# BANK14.net
KiCad netlist of a schematic drawn in Altium Designer
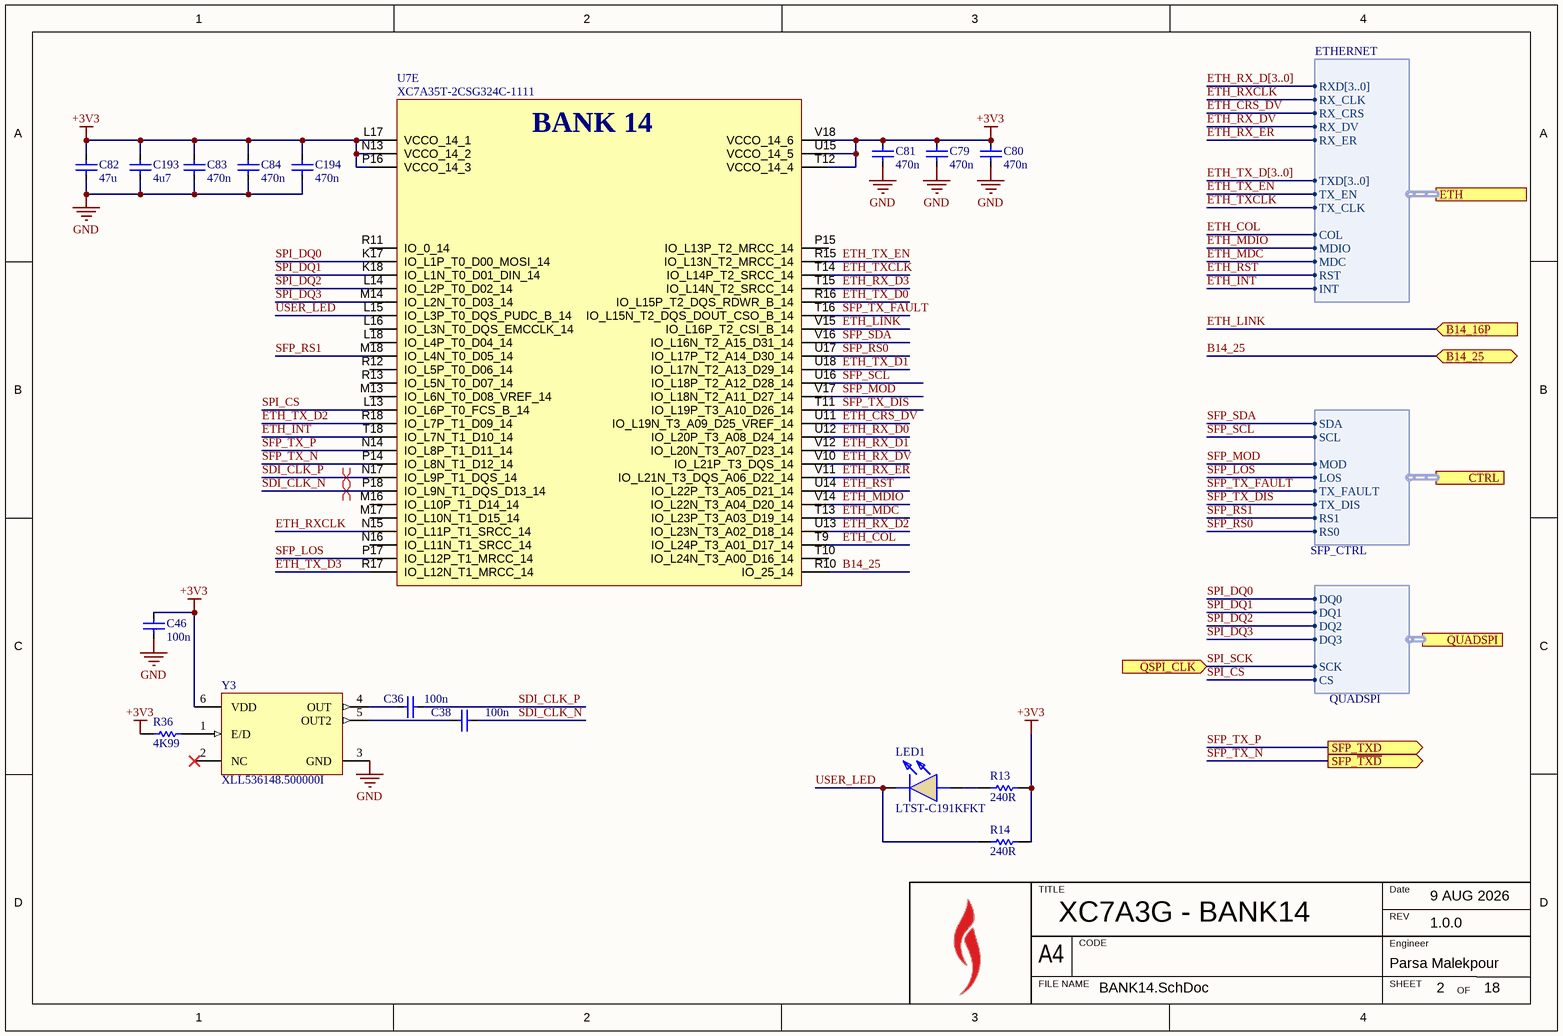
[diagram p0: BANK14.SchDoc]

(export (version "E")
  (design (tool "Eeschema 10.0.6"))
  (components
    (comp (ref "C36")
      (value "100n")
      (footprint "FP-C1005-050-0_05-IPC_C")
      (description "MLCC 100nF ±10% 50V X7R SMD 0402")
      (fields (field (name "VOLTAGE") "50V") (field (name "TOLERANCE") "10%"))
      (libsource (lib "Schlib1") (part "C1005X7R1H104K050BB"))
    )
    (comp (ref "C38")
      (value "100n")
      (footprint "FP-C1005-050-0_05-IPC_C")
      (description "MLCC 100nF ±10% 50V X7R SMD 0402")
      (fields (field (name "VOLTAGE") "50V") (field (name "TOLERANCE") "10%"))
      (libsource (lib "Schlib1") (part "C1005X7R1H104K050BB"))
    )
    (comp (ref "C46")
      (value "100n")
      (footprint "FP-C1005-050-0_05-IPC_C")
      (description "MLCC 100nF ±10% 50V X7R SMD 0402")
      (fields (field (name "VOLTAGE") "50V") (field (name "TOLERANCE") "10%"))
      (libsource (lib "Schlib1") (part "C1005X7R1H104K050BB"))
    )
    (comp (ref "C79")
      (value "470n")
      (footprint "pcblib1:FP-C1005-050-0_05-IPC_C")
      (description "Multilayer Ceramic Capacitors 470nF ±10% 25V X5R SMD 0402")
      (fields (field (name "VOLTAGE") "25V") (field (name "TOLERANCE") "10%"))
      (libsource (lib "Schlib1") (part "C1005X5R1E474K050BB"))
    )
    (comp (ref "C80")
      (value "470n")
      (footprint "pcblib1:FP-C1005-050-0_05-IPC_C")
      (description "Multilayer Ceramic Capacitors 470nF ±10% 25V X5R SMD 0402")
      (fields (field (name "VOLTAGE") "25V") (field (name "TOLERANCE") "10%"))
      (libsource (lib "Schlib1") (part "C1005X5R1E474K050BB"))
    )
    (comp (ref "C81")
      (value "470n")
      (footprint "pcblib1:FP-C1005-050-0_05-IPC_C")
      (description "Multilayer Ceramic Capacitors 470nF ±10% 25V X5R SMD 0402")
      (fields (field (name "VOLTAGE") "25V") (field (name "TOLERANCE") "10%"))
      (libsource (lib "Schlib1") (part "C1005X5R1E474K050BB"))
    )
    (comp (ref "C82")
      (value "47u")
      (footprint "pcblib1:FP-C2012-125-0_2-IPC_C")
      (description "47μF ±20% 10V X5R SMD 0805 Multilayer Ceramic Capacitors")
      (fields (field (name "VOLTAGE") "10V") (field (name "TOLERANCE") "20%"))
      (libsource (lib "Schlib1") (part "C2012X5R1A476M125AC"))
    )
    (comp (ref "C83")
      (value "470n")
      (footprint "pcblib1:FP-C1005-050-0_05-IPC_C")
      (description "Multilayer Ceramic Capacitors 470nF ±10% 25V X5R SMD 0402")
      (fields (field (name "VOLTAGE") "25V") (field (name "TOLERANCE") "10%"))
      (libsource (lib "Schlib1") (part "C1005X5R1E474K050BB"))
    )
    (comp (ref "C84")
      (value "470n")
      (footprint "pcblib1:FP-C1005-050-0_05-IPC_C")
      (description "Multilayer Ceramic Capacitors 470nF ±10% 25V X5R SMD 0402")
      (fields (field (name "VOLTAGE") "25V") (field (name "TOLERANCE") "10%"))
      (libsource (lib "Schlib1") (part "C1005X5R1E474K050BB"))
    )
    (comp (ref "C193")
      (value "4u7")
      (footprint "FP-C1005-050-0_20-0_10-IPC_C")
      (description "4.7UF 10V X5R 0402")
      (fields (field (name "TOLERANCE") "10%") (field (name "PART NUMBER") "C1005X5R1A475K050BE"))
      (libsource (lib "Schlib1") (part "C1005X5R1A475K050BE"))
    )
    (comp (ref "C194")
      (value "470n")
      (footprint "pcblib1:FP-C1005-050-0_05-IPC_C")
      (description "Multilayer Ceramic Capacitors 470nF ±10% 25V X5R SMD 0402")
      (fields (field (name "VOLTAGE") "25V") (field (name "TOLERANCE") "10%"))
      (libsource (lib "Schlib1") (part "C1005X5R1E474K050BB"))
    )
    (comp (ref "LED1")
      (value "LTST-C191KFKT")
      (footprint "LEDC1608X55N")
      (description "LED")
      (fields (field (name "MOUSER PART NUMBER") "859-LTST-C191KFKT") (field (name "MANUFACTURER") "Lite-On"))
      (libsource (lib "Schlib1") (part "LTST-C191KFKT"))
    )
    (comp (ref "R13")
      (value "240R")
      (footprint "pcblib1:RESC1005X40X25LL05T10")
      (description "240R 0.063W 1% 0402 (1005 Metric)  SMD")
      (fields (field (name "POWER") "0.063 W") (field (name "TOLERANCE") "1 %"))
      (libsource (lib "Schlib1") (part "RC0402FR-07240RL"))
    )
    (comp (ref "R14")
      (value "240R")
      (footprint "pcblib1:RESC1005X40X25LL05T10")
      (description "240R 0.063W 1% 0402 (1005 Metric)  SMD")
      (fields (field (name "POWER") "0.063 W") (field (name "TOLERANCE") "1 %"))
      (libsource (lib "Schlib1") (part "RC0402FR-07240RL"))
    )
    (comp (ref "R36")
      (value "4K99")
      (footprint "RESC1005X40X25LL05T10")
      (fields (field (name "MANUFACTURER") "Yageo / Phycomp") (field (name "PART NUMBER") "RC0402FR-074K99L"))
      (libsource (lib "Schlib1") (part "RC0402FR-074K99L"))
    )
    (comp (ref "U7")
      (value "XC7A35T-2CSG324C-1111")
      (footprint "PCBLIB1:BGA324C80P18X18_1500X1500X150")
      (description "Integrated Circuit")
      (fields
        (field (name "MANUFACTURER_PART_NUMBER") "XC7A35T-2CSG324C")
        (field (name "MOUSER PART NUMBER") "217-XC7A35T-2CSG324C")
      )
      (libsource (lib "Schlib1") (part "XC7A35T-2CSG324C-1111"))
    )
    (comp (ref "Y3")
      (value "XLL536148.500000I")
      (footprint "JS6_MFG")
      (description "Oscillator, 148.5Mhz, Lvds, 5Mm X 3.2Mm Rohs Compliant: Yes")
      (libsource (lib "Schlib1") (part "XLL536148.500000I"))
    )
  )
  (nets
    (net (code "4") (name "+3V3") (class "Default")
      (node (ref "C193") (pin "1") (pinfunction "1_1") (pintype "passive"))
      (node (ref "C194") (pin "1") (pinfunction "1_1") (pintype "passive"))
      (node (ref "C46") (pin "2") (pinfunction "2_2") (pintype "passive"))
      (node (ref "C79") (pin "1") (pinfunction "1_1") (pintype "passive"))
      (node (ref "C80") (pin "1") (pinfunction "1_1") (pintype "passive"))
      (node (ref "C81") (pin "1") (pinfunction "1_1") (pintype "passive"))
      (node (ref "C82") (pin "1") (pinfunction "1_1") (pintype "passive"))
      (node (ref "C83") (pin "1") (pinfunction "1_1") (pintype "passive"))
      (node (ref "C84") (pin "1") (pinfunction "1_1") (pintype "passive"))
      (node (ref "R13") (pin "2") (pinfunction "2_2") (pintype "passive"))
      (node (ref "R14") (pin "2") (pinfunction "2_2") (pintype "passive"))
      (node (ref "R36") (pin "1") (pinfunction "1_1") (pintype "passive"))
      (node (ref "U7") (pin "L17") (pinfunction "VCCO_14_1_L17") (pintype "passive"))
      (node (ref "U7") (pin "N13") (pinfunction "VCCO_14_2_N13") (pintype "passive"))
      (node (ref "U7") (pin "P16") (pinfunction "VCCO_14_3_P16") (pintype "passive"))
      (node (ref "U7") (pin "T12") (pinfunction "VCCO_14_4_T12") (pintype "passive"))
      (node (ref "U7") (pin "U15") (pinfunction "VCCO_14_5_U15") (pintype "passive"))
      (node (ref "U7") (pin "V18") (pinfunction "VCCO_14_6_V18") (pintype "passive"))
      (node (ref "Y3") (pin "6") (pinfunction "VDD_6") (pintype "power_in"))
    )
    (net (code "5") (name "/B14_25") (class "Default")
      (node (ref "U7") (pin "R10") (pinfunction "IO_25_14_R10") (pintype "passive"))
    )
    (net (code "6") (name "/ETH_COL") (class "Default")
      (node (ref "U7") (pin "T9") (pinfunction "IO_L24P_T3_A01_D17_14_T9") (pintype "passive"))
    )
    (net (code "7") (name "/ETH_CRS_DV") (class "Default")
      (node (ref "U7") (pin "U11") (pinfunction "IO_L19N_T3_A09_D25_VREF_14_U11") (pintype "passive"))
    )
    (net (code "8") (name "/ETH_INT") (class "Default")
      (node (ref "U7") (pin "T18") (pinfunction "IO_L7N_T1_D10_14_T18") (pintype "passive"))
    )
    (net (code "9") (name "/ETH_LINK") (class "Default")
      (node (ref "U7") (pin "V15") (pinfunction "IO_L16P_T2_CSI_B_14_V15") (pintype "passive"))
    )
    (net (code "10") (name "/ETH_MDC") (class "Default")
      (node (ref "U7") (pin "T13") (pinfunction "IO_L23P_T3_A03_D19_14_T13") (pintype "passive"))
    )
    (net (code "11") (name "/ETH_MDIO") (class "Default")
      (node (ref "U7") (pin "V14") (pinfunction "IO_L22N_T3_A04_D20_14_V14") (pintype "passive"))
    )
    (net (code "12") (name "/ETH_RST") (class "Default")
      (node (ref "U7") (pin "U14") (pinfunction "IO_L22P_T3_A05_D21_14_U14") (pintype "passive"))
    )
    (net (code "13") (name "/ETH_RXCLK") (class "Default")
      (node (ref "U7") (pin "N15") (pinfunction "IO_L11P_T1_SRCC_14_N15") (pintype "passive"))
    )
    (net (code "14") (name "/ETH_RX_D0") (class "Default")
      (node (ref "U7") (pin "U12") (pinfunction "IO_L20P_T3_A08_D24_14_U12") (pintype "passive"))
    )
    (net (code "15") (name "/ETH_RX_D1") (class "Default")
      (node (ref "U7") (pin "V12") (pinfunction "IO_L20N_T3_A07_D23_14_V12") (pintype "passive"))
    )
    (net (code "16") (name "/ETH_RX_D2") (class "Default")
      (node (ref "U7") (pin "U13") (pinfunction "IO_L23N_T3_A02_D18_14_U13") (pintype "passive"))
    )
    (net (code "17") (name "/ETH_RX_D3") (class "Default")
      (node (ref "U7") (pin "T15") (pinfunction "IO_L14N_T2_SRCC_14_T15") (pintype "passive"))
    )
    (net (code "18") (name "/ETH_RX_DV") (class "Default")
      (node (ref "U7") (pin "V10") (pinfunction "IO_L21P_T3_DQS_14_V10") (pintype "passive"))
    )
    (net (code "20") (name "/ETH_RX_ER") (class "Default")
      (node (ref "U7") (pin "V11") (pinfunction "IO_L21N_T3_DQS_A06_D22_14_V11") (pintype "passive"))
    )
    (net (code "21") (name "/ETH_TXCLK") (class "Default")
      (node (ref "U7") (pin "T14") (pinfunction "IO_L14P_T2_SRCC_14_T14") (pintype "passive"))
    )
    (net (code "22") (name "/ETH_TX_D0") (class "Default")
      (node (ref "U7") (pin "R16") (pinfunction "IO_L15P_T2_DQS_RDWR_B_14_R16") (pintype "passive"))
    )
    (net (code "23") (name "/ETH_TX_D1") (class "Default")
      (node (ref "U7") (pin "U18") (pinfunction "IO_L17N_T2_A13_D29_14_U18") (pintype "passive"))
    )
    (net (code "24") (name "/ETH_TX_D2") (class "Default")
      (node (ref "U7") (pin "R18") (pinfunction "IO_L7P_T1_D09_14_R18") (pintype "passive"))
    )
    (net (code "25") (name "/ETH_TX_D3") (class "Default")
      (node (ref "U7") (pin "R17") (pinfunction "IO_L12N_T1_MRCC_14_R17") (pintype "passive"))
    )
    (net (code "27") (name "/ETH_TX_EN") (class "Default")
      (node (ref "U7") (pin "R15") (pinfunction "IO_L13N_T2_MRCC_14_R15") (pintype "passive"))
    )
    (net (code "28") (name "/SDI_CLK_N") (class "Default")
      (node (ref "C38") (pin "2") (pinfunction "2_2") (pintype "passive"))
      (node (ref "U7") (pin "P18") (pinfunction "IO_L9N_T1_DQS_D13_14_P18") (pintype "passive"))
    )
    (net (code "29") (name "/SDI_CLK_P") (class "Default")
      (node (ref "C36") (pin "2") (pinfunction "2_2") (pintype "passive"))
      (node (ref "U7") (pin "N17") (pinfunction "IO_L9P_T1_DQS_14_N17") (pintype "passive"))
    )
    (net (code "30") (name "/SFP_LOS") (class "Default")
      (node (ref "U7") (pin "P17") (pinfunction "IO_L12P_T1_MRCC_14_P17") (pintype "passive"))
    )
    (net (code "31") (name "/SFP_MOD") (class "Default")
      (node (ref "U7") (pin "V17") (pinfunction "IO_L18N_T2_A11_D27_14_V17") (pintype "passive"))
    )
    (net (code "32") (name "/SFP_RS0") (class "Default")
      (node (ref "U7") (pin "U17") (pinfunction "IO_L17P_T2_A14_D30_14_U17") (pintype "passive"))
    )
    (net (code "33") (name "/SFP_RS1") (class "Default")
      (node (ref "U7") (pin "M18") (pinfunction "IO_L4N_T0_D05_14_M18") (pintype "passive"))
    )
    (net (code "34") (name "/SFP_SCL") (class "Default")
      (node (ref "U7") (pin "U16") (pinfunction "IO_L18P_T2_A12_D28_14_U16") (pintype "passive"))
    )
    (net (code "35") (name "/SFP_SDA") (class "Default")
      (node (ref "U7") (pin "V16") (pinfunction "IO_L16N_T2_A15_D31_14_V16") (pintype "passive"))
    )
    (net (code "36") (name "/SFP_TX_DIS") (class "Default")
      (node (ref "U7") (pin "T11") (pinfunction "IO_L19P_T3_A10_D26_14_T11") (pintype "passive"))
    )
    (net (code "37") (name "/SFP_TX_FAULT") (class "Default")
      (node (ref "U7") (pin "T16") (pinfunction "IO_L15N_T2_DQS_DOUT_CSO_B_14_T16") (pintype "passive"))
    )
    (net (code "38") (name "/SFP_TX_N") (class "Default")
      (node (ref "U7") (pin "P14") (pinfunction "IO_L8N_T1_D12_14_P14") (pintype "passive"))
    )
    (net (code "39") (name "/SFP_TX_P") (class "Default")
      (node (ref "U7") (pin "N14") (pinfunction "IO_L8P_T1_D11_14_N14") (pintype "passive"))
    )
    (net (code "40") (name "/SPI_CS") (class "Default")
      (node (ref "U7") (pin "L13") (pinfunction "IO_L6P_T0_FCS_B_14_L13") (pintype "passive"))
    )
    (net (code "41") (name "/SPI_DQ0") (class "Default")
      (node (ref "U7") (pin "K17") (pinfunction "IO_L1P_T0_D00_MOSI_14_K17") (pintype "passive"))
    )
    (net (code "42") (name "/SPI_DQ1") (class "Default")
      (node (ref "U7") (pin "K18") (pinfunction "IO_L1N_T0_D01_DIN_14_K18") (pintype "passive"))
    )
    (net (code "43") (name "/SPI_DQ2") (class "Default")
      (node (ref "U7") (pin "L14") (pinfunction "IO_L2P_T0_D02_14_L14") (pintype "passive"))
    )
    (net (code "44") (name "/SPI_DQ3") (class "Default")
      (node (ref "U7") (pin "M14") (pinfunction "IO_L2N_T0_D03_14_M14") (pintype "passive"))
    )
    (net (code "46") (name "/USER_LED") (class "Default")
      (node (ref "LED1") (pin "1") (pinfunction "K_1") (pintype "passive"))
      (node (ref "R14") (pin "1") (pinfunction "1_1") (pintype "passive"))
      (node (ref "U7") (pin "L15") (pinfunction "IO_L3P_T0_DQS_PUDC_B_14_L15") (pintype "passive"))
    )
    (net (code "50") (name "GND") (class "Default")
      (node (ref "C193") (pin "2") (pinfunction "2_2") (pintype "passive"))
      (node (ref "C194") (pin "2") (pinfunction "2_2") (pintype "passive"))
      (node (ref "C46") (pin "1") (pinfunction "1_1") (pintype "passive"))
      (node (ref "C79") (pin "2") (pinfunction "2_2") (pintype "passive"))
      (node (ref "C80") (pin "2") (pinfunction "2_2") (pintype "passive"))
      (node (ref "C81") (pin "2") (pinfunction "2_2") (pintype "passive"))
      (node (ref "C82") (pin "2") (pinfunction "2_2") (pintype "passive"))
      (node (ref "C83") (pin "2") (pinfunction "2_2") (pintype "passive"))
      (node (ref "C84") (pin "2") (pinfunction "2_2") (pintype "passive"))
      (node (ref "Y3") (pin "3") (pinfunction "GND_3") (pintype "power_in"))
    )
    (net (code "51") (name "Net-(LED1-A)") (class "Default")
      (node (ref "LED1") (pin "2") (pinfunction "A_2") (pintype "passive"))
      (node (ref "R13") (pin "1") (pinfunction "1_1") (pintype "passive"))
    )
    (net (code "52") (name "Net-(Y3-E{slash}D)") (class "Default")
      (node (ref "R36") (pin "2") (pinfunction "2_2") (pintype "passive"))
      (node (ref "Y3") (pin "1") (pinfunction "E/D_1") (pintype "input"))
    )
    (net (code "53") (name "Net-(Y3-OUT)") (class "Default")
      (node (ref "C36") (pin "1") (pinfunction "1_1") (pintype "passive"))
      (node (ref "Y3") (pin "4") (pinfunction "OUT_4") (pintype "output"))
    )
    (net (code "54") (name "Net-(Y3-OUT2)") (class "Default")
      (node (ref "C38") (pin "1") (pinfunction "1_1") (pintype "passive"))
      (node (ref "Y3") (pin "5") (pinfunction "OUT2_5") (pintype "output"))
    )
    (net (code "55") (name "unconnected-(U7E-IO_0_14-PadR11)") (class "Default")
      (node (ref "U7") (pin "R11") (pinfunction "IO_0_14_R11") (pintype "passive"))
    )
    (net (code "56") (name "unconnected-(U7E-IO_L3N_T0_DQS_EMCCLK_14-PadL16)") (class "Default")
      (node (ref "U7") (pin "L16") (pinfunction "IO_L3N_T0_DQS_EMCCLK_14_L16") (pintype "passive"))
    )
    (net (code "57") (name "unconnected-(U7E-IO_L4P_T0_D04_14-PadL18)") (class "Default")
      (node (ref "U7") (pin "L18") (pinfunction "IO_L4P_T0_D04_14_L18") (pintype "passive"))
    )
    (net (code "58") (name "unconnected-(U7E-IO_L5N_T0_D07_14-PadR13)") (class "Default")
      (node (ref "U7") (pin "R13") (pinfunction "IO_L5N_T0_D07_14_R13") (pintype "passive"))
    )
    (net (code "59") (name "unconnected-(U7E-IO_L5P_T0_D06_14-PadR12)") (class "Default")
      (node (ref "U7") (pin "R12") (pinfunction "IO_L5P_T0_D06_14_R12") (pintype "passive"))
    )
    (net (code "60") (name "unconnected-(U7E-IO_L6N_T0_D08_VREF_14-PadM13)") (class "Default")
      (node (ref "U7") (pin "M13") (pinfunction "IO_L6N_T0_D08_VREF_14_M13") (pintype "passive"))
    )
    (net (code "61") (name "unconnected-(U7E-IO_L10N_T1_D15_14-PadM17)") (class "Default")
      (node (ref "U7") (pin "M17") (pinfunction "IO_L10N_T1_D15_14_M17") (pintype "passive"))
    )
    (net (code "62") (name "unconnected-(U7E-IO_L10P_T1_D14_14-PadM16)") (class "Default")
      (node (ref "U7") (pin "M16") (pinfunction "IO_L10P_T1_D14_14_M16") (pintype "passive"))
    )
    (net (code "63") (name "unconnected-(U7E-IO_L11N_T1_SRCC_14-PadN16)") (class "Default")
      (node (ref "U7") (pin "N16") (pinfunction "IO_L11N_T1_SRCC_14_N16") (pintype "passive"))
    )
    (net (code "64") (name "unconnected-(U7E-IO_L13P_T2_MRCC_14-PadP15)") (class "Default")
      (node (ref "U7") (pin "P15") (pinfunction "IO_L13P_T2_MRCC_14_P15") (pintype "passive"))
    )
    (net (code "65") (name "unconnected-(U7E-IO_L24N_T3_A00_D16_14-PadT10)") (class "Default")
      (node (ref "U7") (pin "T10") (pinfunction "IO_L24N_T3_A00_D16_14_T10") (pintype "passive"))
    )
    (net (code "66") (name "unconnected-(Y3-NC-Pad2)") (class "Default")
      (node (ref "Y3") (pin "2") (pinfunction "NC_2") (pintype "passive+no_connect"))
    )
  )
)
